# main.net
KiCad netlist of a schematic drawn in EAGLE
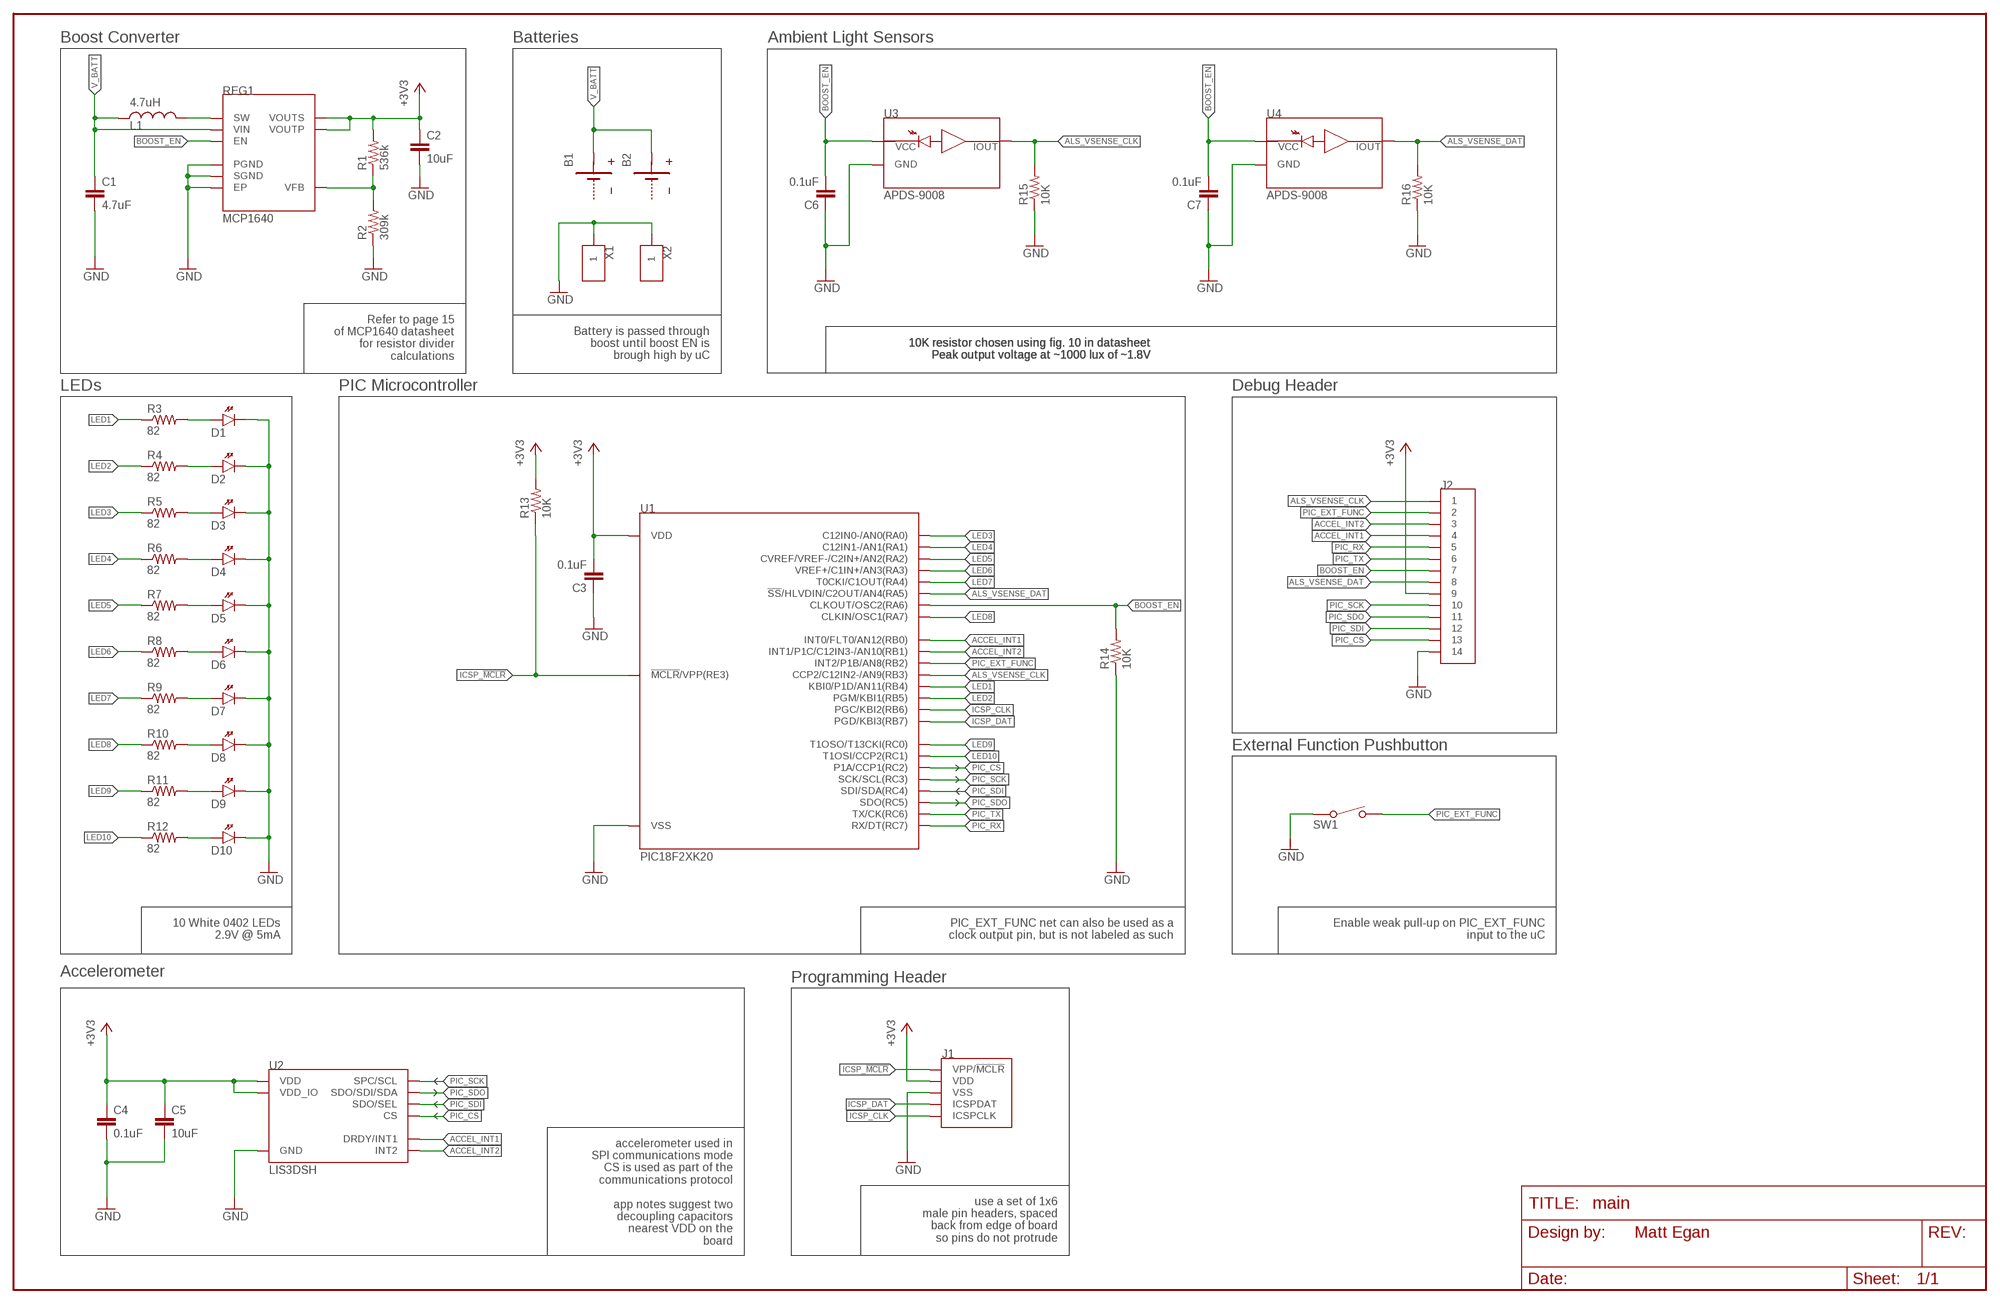
[diagram p0: schematic, sheet 1]

(export (version "E")
  (design (tool "Eeschema 10.0.6"))
  (components
    (comp (ref "B1")
      (value "BATTERY-POS-HALF")
      (footprint "eagle-import:CR20XX-PLATED")
      (libsource (lib "eagle-import") (part "BATTERY-POS-HALF"))
    )
    (comp (ref "B2")
      (value "BATTERY-POS-HALF")
      (footprint "eagle-import:CR20XX-PLATED")
      (libsource (lib "eagle-import") (part "BATTERY-POS-HALF"))
    )
    (comp (ref "C1")
      (value "4.7uF")
      (footprint "eagle-import:SMD-0603")
      (libsource (lib "eagle-import") (part "CAPACITOR0603"))
    )
    (comp (ref "C2")
      (value "10uF")
      (footprint "eagle-import:SMD-0603")
      (libsource (lib "eagle-import") (part "CAPACITOR0603"))
    )
    (comp (ref "C3")
      (value "0.1uF")
      (footprint "eagle-import:SMD-0805")
      (libsource (lib "eagle-import") (part "CAPACITOR0805"))
    )
    (comp (ref "C4")
      (value "0.1uF")
      (footprint "eagle-import:SMD-0805")
      (libsource (lib "eagle-import") (part "CAPACITOR0805"))
    )
    (comp (ref "C5")
      (value "10uF")
      (footprint "eagle-import:SMD-0805")
      (libsource (lib "eagle-import") (part "CAPACITOR0805"))
    )
    (comp (ref "C6")
      (value "0.1uF")
      (footprint "eagle-import:SMD-0805")
      (libsource (lib "eagle-import") (part "CAPACITOR0805"))
    )
    (comp (ref "C7")
      (value "0.1uF")
      (footprint "eagle-import:SMD-0805")
      (libsource (lib "eagle-import") (part "CAPACITOR0805"))
    )
    (comp (ref "D1")
      (value "LED0603")
      (footprint "eagle-import:SMD-0603-P")
      (libsource (lib "eagle-import") (part "LED0603"))
    )
    (comp (ref "D2")
      (value "LED0603")
      (footprint "eagle-import:SMD-0603-P")
      (libsource (lib "eagle-import") (part "LED0603"))
    )
    (comp (ref "D3")
      (value "LED0603")
      (footprint "eagle-import:SMD-0603-P")
      (libsource (lib "eagle-import") (part "LED0603"))
    )
    (comp (ref "D4")
      (value "LED0603")
      (footprint "eagle-import:SMD-0603-P")
      (libsource (lib "eagle-import") (part "LED0603"))
    )
    (comp (ref "D5")
      (value "LED0603")
      (footprint "eagle-import:SMD-0603-P")
      (libsource (lib "eagle-import") (part "LED0603"))
    )
    (comp (ref "D6")
      (value "LED0603")
      (footprint "eagle-import:SMD-0603-P")
      (libsource (lib "eagle-import") (part "LED0603"))
    )
    (comp (ref "D7")
      (value "LED0603")
      (footprint "eagle-import:SMD-0603-P")
      (libsource (lib "eagle-import") (part "LED0603"))
    )
    (comp (ref "D8")
      (value "LED0603")
      (footprint "eagle-import:SMD-0603-P")
      (libsource (lib "eagle-import") (part "LED0603"))
    )
    (comp (ref "D9")
      (value "LED0603")
      (footprint "eagle-import:SMD-0603-P")
      (libsource (lib "eagle-import") (part "LED0603"))
    )
    (comp (ref "D10")
      (value "LED0603")
      (footprint "eagle-import:SMD-0603-P")
      (libsource (lib "eagle-import") (part "LED0603"))
    )
    (comp (ref "J1")
      (value "ICSP-HEADER1X6-0.1-ICSP-PADS")
      (footprint "eagle-import:1X6-0.1-ICSP-PADS")
      (libsource (lib "eagle-import") (part "ICSP-HEADER1X6-0.1-ICSP-PADS"))
    )
    (comp (ref "J2")
      (value "HEADER-141X14-0.05-PADS")
      (footprint "eagle-import:1X14-0.05-PADS")
      (libsource (lib "eagle-import") (part "HEADER-141X14-0.05-PADS"))
    )
    (comp (ref "L1")
      (value "4.7uH")
      (footprint "eagle-import:VLF403210MT")
      (libsource (lib "eagle-import") (part "INDUCTOR"))
    )
    (comp (ref "R1")
      (value "536k")
      (footprint "eagle-import:SMD-0603")
      (libsource (lib "eagle-import") (part "RESISTOR0603"))
    )
    (comp (ref "R2")
      (value "309k")
      (footprint "eagle-import:SMD-0603")
      (libsource (lib "eagle-import") (part "RESISTOR0603"))
    )
    (comp (ref "R3")
      (value "82")
      (footprint "eagle-import:SMD-0603")
      (libsource (lib "eagle-import") (part "RESISTOR0603"))
    )
    (comp (ref "R4")
      (value "82")
      (footprint "eagle-import:SMD-0603")
      (libsource (lib "eagle-import") (part "RESISTOR0603"))
    )
    (comp (ref "R5")
      (value "82")
      (footprint "eagle-import:SMD-0603")
      (libsource (lib "eagle-import") (part "RESISTOR0603"))
    )
    (comp (ref "R6")
      (value "82")
      (footprint "eagle-import:SMD-0603")
      (libsource (lib "eagle-import") (part "RESISTOR0603"))
    )
    (comp (ref "R7")
      (value "82")
      (footprint "eagle-import:SMD-0603")
      (libsource (lib "eagle-import") (part "RESISTOR0603"))
    )
    (comp (ref "R8")
      (value "82")
      (footprint "eagle-import:SMD-0603")
      (libsource (lib "eagle-import") (part "RESISTOR0603"))
    )
    (comp (ref "R9")
      (value "82")
      (footprint "eagle-import:SMD-0603")
      (libsource (lib "eagle-import") (part "RESISTOR0603"))
    )
    (comp (ref "R10")
      (value "82")
      (footprint "eagle-import:SMD-0603")
      (libsource (lib "eagle-import") (part "RESISTOR0603"))
    )
    (comp (ref "R11")
      (value "82")
      (footprint "eagle-import:SMD-0603")
      (libsource (lib "eagle-import") (part "RESISTOR0603"))
    )
    (comp (ref "R12")
      (value "82")
      (footprint "eagle-import:SMD-0603")
      (libsource (lib "eagle-import") (part "RESISTOR0603"))
    )
    (comp (ref "R13")
      (value "10K")
      (footprint "eagle-import:SMD-0603")
      (libsource (lib "eagle-import") (part "RESISTOR0603"))
    )
    (comp (ref "R14")
      (value "10K")
      (footprint "eagle-import:SMD-0603")
      (libsource (lib "eagle-import") (part "RESISTOR0603"))
    )
    (comp (ref "R15")
      (value "10K")
      (footprint "eagle-import:SMD-0603")
      (libsource (lib "eagle-import") (part "RESISTOR0603"))
    )
    (comp (ref "R16")
      (value "10K")
      (footprint "eagle-import:SMD-0603")
      (libsource (lib "eagle-import") (part "RESISTOR0603"))
    )
    (comp (ref "REG1")
      (value "MCP1640")
      (footprint "eagle-import:DFN-8(2X3)")
      (libsource (lib "eagle-import") (part "MCP1640"))
    )
    (comp (ref "SW1")
      (value "B3U-3000P")
      (footprint "eagle-import:B3U-3000P")
      (libsource (lib "eagle-import") (part "B3U-3000P"))
    )
    (comp (ref "U1")
      (value "PIC18F2XK20")
      (footprint "eagle-import:QFN-28")
      (libsource (lib "eagle-import") (part "PIC18F2XK20"))
    )
    (comp (ref "U2")
      (value "LIS3DSH")
      (footprint "eagle-import:LGA-16")
      (libsource (lib "eagle-import") (part "LIS3DSH"))
    )
    (comp (ref "U3")
      (value "APDS-9008")
      (footprint "eagle-import:AVAGO-CHIPLED6")
      (libsource (lib "eagle-import") (part "APDS-9008"))
    )
    (comp (ref "U4")
      (value "APDS-9008")
      (footprint "eagle-import:AVAGO-CHIPLED6")
      (libsource (lib "eagle-import") (part "APDS-9008"))
    )
    (comp (ref "X1")
      (value "TE-2199248-X")
      (footprint "eagle-import:TE-2199248-X")
      (libsource (lib "eagle-import") (part "TE-2199248-X"))
    )
    (comp (ref "X2")
      (value "TE-2199248-X")
      (footprint "eagle-import:TE-2199248-X")
      (libsource (lib "eagle-import") (part "TE-2199248-X"))
    )
  )
  (nets
    (net (code "1") (name "+3V3") (class "Default")
      (node (ref "C2") (pin "1") (pinfunction "1_1") (pintype "passive"))
      (node (ref "C3") (pin "2") (pinfunction "2_2") (pintype "passive"))
      (node (ref "C4") (pin "1") (pinfunction "1_1") (pintype "passive"))
      (node (ref "C5") (pin "1") (pinfunction "1_1") (pintype "passive"))
      (node (ref "J1") (pin "P$2") (pinfunction "VDD_P$2") (pintype "bidirectional"))
      (node (ref "J2") (pin "P$9") (pinfunction "9_P$9") (pintype "bidirectional"))
      (node (ref "R1") (pin "2") (pinfunction "2_2") (pintype "passive"))
      (node (ref "R13") (pin "2") (pinfunction "2_2") (pintype "passive"))
      (node (ref "REG1") (pin "6") (pinfunction "VOUTP_6") (pintype "bidirectional"))
      (node (ref "REG1") (pin "7") (pinfunction "VOUTS_7") (pintype "bidirectional"))
      (node (ref "U1") (pin "P$17") (pinfunction "VDD_P$17") (pintype "bidirectional"))
      (node (ref "U2") (pin "P$1") (pinfunction "VDD_IO_P$1") (pintype "power_in"))
      (node (ref "U2") (pin "P$14") (pinfunction "VDD_P$14") (pintype "power_in"))
      (node (ref "U2") (pin "P$15") (pinfunction "VDD_P$15") (pintype "power_in"))
    )
    (net (code "2") (name "/ICSP_~{MCLR}") (class "Default")
      (node (ref "J1") (pin "P$1") (pinfunction "VPP/~{MCLR}_P$1") (pintype "bidirectional"))
      (node (ref "R13") (pin "1") (pinfunction "1_1") (pintype "passive"))
      (node (ref "U1") (pin "P$26") (pinfunction "~{MCLR}/VPP(RE3)_P$26") (pintype "bidirectional"))
    )
    (net (code "3") (name "ACCEL_INT1") (class "Default")
      (node (ref "J2") (pin "P$4") (pinfunction "4_P$4") (pintype "bidirectional"))
      (node (ref "U1") (pin "P$18") (pinfunction "INT0/FLT0/AN12(RB0)_P$18") (pintype "bidirectional"))
      (node (ref "U2") (pin "P$11") (pinfunction "DRDY/INT1_P$11") (pintype "bidirectional"))
    )
    (net (code "4") (name "ACCEL_INT2") (class "Default")
      (node (ref "J2") (pin "P$3") (pinfunction "3_P$3") (pintype "bidirectional"))
      (node (ref "U1") (pin "P$19") (pinfunction "INT1/P1C/C12IN3-/AN10(RB1)_P$19") (pintype "bidirectional"))
      (node (ref "U2") (pin "P$9") (pinfunction "INT2_P$9") (pintype "bidirectional"))
    )
    (net (code "5") (name "ALS_VSENSE_CLK") (class "Default")
      (node (ref "J2") (pin "P$1") (pinfunction "1_P$1") (pintype "bidirectional"))
      (node (ref "R15") (pin "2") (pinfunction "2_2") (pintype "passive"))
      (node (ref "U1") (pin "P$21") (pinfunction "CCP2/C12IN2-/AN9(RB3)_P$21") (pintype "bidirectional"))
      (node (ref "U3") (pin "P$6") (pinfunction "P$IOUT_P$6") (pintype "bidirectional"))
    )
    (net (code "6") (name "ALS_VSENSE_DAT") (class "Default")
      (node (ref "J2") (pin "P$8") (pinfunction "8_P$8") (pintype "bidirectional"))
      (node (ref "R16") (pin "2") (pinfunction "2_2") (pintype "passive"))
      (node (ref "U1") (pin "P$4") (pinfunction "~{SS}/HLVDIN/C2OUT/AN4(RA5)_P$4") (pintype "bidirectional"))
      (node (ref "U4") (pin "P$6") (pinfunction "P$IOUT_P$6") (pintype "bidirectional"))
    )
    (net (code "7") (name "BOOST_EN") (class "Default")
      (node (ref "C6") (pin "2") (pinfunction "2_2") (pintype "passive"))
      (node (ref "C7") (pin "2") (pinfunction "2_2") (pintype "passive"))
      (node (ref "J2") (pin "P$7") (pinfunction "7_P$7") (pintype "bidirectional"))
      (node (ref "R14") (pin "2") (pinfunction "2_2") (pintype "passive"))
      (node (ref "REG1") (pin "4") (pinfunction "EN_4") (pintype "bidirectional"))
      (node (ref "U1") (pin "P$7") (pinfunction "CLKOUT/OSC2(RA6)_P$7") (pintype "bidirectional"))
      (node (ref "U3") (pin "P$1") (pinfunction "P$VCC_P$1") (pintype "bidirectional"))
      (node (ref "U4") (pin "P$1") (pinfunction "P$VCC_P$1") (pintype "bidirectional"))
    )
    (net (code "8") (name "GND") (class "Default")
      (node (ref "C1") (pin "2") (pinfunction "2_2") (pintype "passive"))
      (node (ref "C2") (pin "2") (pinfunction "2_2") (pintype "passive"))
      (node (ref "C3") (pin "1") (pinfunction "1_1") (pintype "passive"))
      (node (ref "C4") (pin "2") (pinfunction "2_2") (pintype "passive"))
      (node (ref "C5") (pin "2") (pinfunction "2_2") (pintype "passive"))
      (node (ref "C6") (pin "1") (pinfunction "1_1") (pintype "passive"))
      (node (ref "C7") (pin "1") (pinfunction "1_1") (pintype "passive"))
      (node (ref "D1") (pin "-") (pinfunction "-_-") (pintype "bidirectional"))
      (node (ref "D10") (pin "-") (pinfunction "-_-") (pintype "bidirectional"))
      (node (ref "D2") (pin "-") (pinfunction "-_-") (pintype "bidirectional"))
      (node (ref "D3") (pin "-") (pinfunction "-_-") (pintype "bidirectional"))
      (node (ref "D4") (pin "-") (pinfunction "-_-") (pintype "bidirectional"))
      (node (ref "D5") (pin "-") (pinfunction "-_-") (pintype "bidirectional"))
      (node (ref "D6") (pin "-") (pinfunction "-_-") (pintype "bidirectional"))
      (node (ref "D7") (pin "-") (pinfunction "-_-") (pintype "bidirectional"))
      (node (ref "D8") (pin "-") (pinfunction "-_-") (pintype "bidirectional"))
      (node (ref "D9") (pin "-") (pinfunction "-_-") (pintype "bidirectional"))
      (node (ref "J1") (pin "P$3") (pinfunction "VSS_P$3") (pintype "bidirectional"))
      (node (ref "J2") (pin "P$14") (pinfunction "14_P$14") (pintype "bidirectional"))
      (node (ref "R14") (pin "1") (pinfunction "1_1") (pintype "passive"))
      (node (ref "R15") (pin "1") (pinfunction "1_1") (pintype "passive"))
      (node (ref "R16") (pin "1") (pinfunction "1_1") (pintype "passive"))
      (node (ref "R2") (pin "1") (pinfunction "1_1") (pintype "passive"))
      (node (ref "REG1") (pin "2") (pinfunction "SGND_2") (pintype "bidirectional"))
      (node (ref "REG1") (pin "3") (pinfunction "PGND_3") (pintype "bidirectional"))
      (node (ref "REG1") (pin "EP") (pinfunction "EP_EP") (pintype "bidirectional"))
      (node (ref "SW1") (pin "SW$1") (pinfunction "1_SW$1") (pintype "bidirectional"))
      (node (ref "U1") (pin "P$16") (pinfunction "VSS_P$16") (pintype "bidirectional"))
      (node (ref "U1") (pin "P$5") (pinfunction "VSS_P$5") (pintype "bidirectional"))
      (node (ref "U2") (pin "P$10") (pinfunction "GND_P$10") (pintype "power_in"))
      (node (ref "U2") (pin "P$12") (pinfunction "GND_P$12") (pintype "power_in"))
      (node (ref "U2") (pin "P$13") (pinfunction "GND_P$13") (pintype "power_in"))
      (node (ref "U2") (pin "P$16") (pinfunction "GND_P$16") (pintype "power_in"))
      (node (ref "U2") (pin "P$5") (pinfunction "GND_P$5") (pintype "power_in"))
      (node (ref "U3") (pin "P$4") (pinfunction "GND_P$4") (pintype "bidirectional"))
      (node (ref "U4") (pin "P$4") (pinfunction "GND_P$4") (pintype "bidirectional"))
      (node (ref "X1") (pin "P$1") (pinfunction "1_P$1") (pintype "bidirectional"))
      (node (ref "X1") (pin "P$2") (pinfunction "1_P$2") (pintype "bidirectional"))
      (node (ref "X2") (pin "P$1") (pinfunction "1_P$1") (pintype "bidirectional"))
      (node (ref "X2") (pin "P$2") (pinfunction "1_P$2") (pintype "bidirectional"))
    )
    (net (code "9") (name "ICSP_CLK") (class "Default")
      (node (ref "J1") (pin "P$5") (pinfunction "ICSPCLK_P$5") (pintype "bidirectional"))
      (node (ref "U1") (pin "P$24") (pinfunction "PGC/KBI2(RB6)_P$24") (pintype "bidirectional"))
    )
    (net (code "10") (name "ICSP_DAT") (class "Default")
      (node (ref "J1") (pin "P$4") (pinfunction "ICSPDAT_P$4") (pintype "bidirectional"))
      (node (ref "U1") (pin "P$25") (pinfunction "PGD/KBI3(RB7)_P$25") (pintype "bidirectional"))
    )
    (net (code "11") (name "LED1") (class "Default")
      (node (ref "R3") (pin "1") (pinfunction "1_1") (pintype "passive"))
      (node (ref "U1") (pin "P$22") (pinfunction "KBI0/P1D/AN11(RB4)_P$22") (pintype "bidirectional"))
    )
    (net (code "12") (name "LED2") (class "Default")
      (node (ref "R4") (pin "1") (pinfunction "1_1") (pintype "passive"))
      (node (ref "U1") (pin "P$23") (pinfunction "PGM/KBI1(RB5)_P$23") (pintype "bidirectional"))
    )
    (net (code "13") (name "LED3") (class "Default")
      (node (ref "R5") (pin "1") (pinfunction "1_1") (pintype "passive"))
      (node (ref "U1") (pin "P$27") (pinfunction "C12IN0-/AN0(RA0)_P$27") (pintype "bidirectional"))
    )
    (net (code "14") (name "LED4") (class "Default")
      (node (ref "R6") (pin "1") (pinfunction "1_1") (pintype "passive"))
      (node (ref "U1") (pin "P$28") (pinfunction "C12IN1-/AN1(RA1)_P$28") (pintype "bidirectional"))
    )
    (net (code "15") (name "LED5") (class "Default")
      (node (ref "R7") (pin "1") (pinfunction "1_1") (pintype "passive"))
      (node (ref "U1") (pin "P$1") (pinfunction "CVREF/VREF-/C2IN+/AN2(RA2)_P$1") (pintype "bidirectional"))
    )
    (net (code "16") (name "LED6") (class "Default")
      (node (ref "R8") (pin "1") (pinfunction "1_1") (pintype "passive"))
      (node (ref "U1") (pin "P$2") (pinfunction "VREF+/C1IN+/AN3(RA3)_P$2") (pintype "bidirectional"))
    )
    (net (code "17") (name "LED7") (class "Default")
      (node (ref "R9") (pin "1") (pinfunction "1_1") (pintype "passive"))
      (node (ref "U1") (pin "P$3") (pinfunction "T0CKI/C1OUT(RA4)_P$3") (pintype "bidirectional"))
    )
    (net (code "18") (name "LED8") (class "Default")
      (node (ref "R10") (pin "1") (pinfunction "1_1") (pintype "passive"))
      (node (ref "U1") (pin "P$6") (pinfunction "CLKIN/OSC1(RA7)_P$6") (pintype "bidirectional"))
    )
    (net (code "19") (name "LED9") (class "Default")
      (node (ref "R11") (pin "1") (pinfunction "1_1") (pintype "passive"))
      (node (ref "U1") (pin "P$8") (pinfunction "T1OSO/T13CKI(RC0)_P$8") (pintype "bidirectional"))
    )
    (net (code "20") (name "LED10") (class "Default")
      (node (ref "R12") (pin "1") (pinfunction "1_1") (pintype "passive"))
      (node (ref "U1") (pin "P$9") (pinfunction "T1OSI/CCP2(RC1)_P$9") (pintype "bidirectional"))
    )
    (net (code "21") (name "Net-(D1-Pad+)") (class "Default")
      (node (ref "D1") (pin "+") (pinfunction "+_+") (pintype "input"))
      (node (ref "R3") (pin "2") (pinfunction "2_2") (pintype "passive"))
    )
    (net (code "22") (name "Net-(D2-Pad+)") (class "Default")
      (node (ref "D2") (pin "+") (pinfunction "+_+") (pintype "input"))
      (node (ref "R4") (pin "2") (pinfunction "2_2") (pintype "passive"))
    )
    (net (code "23") (name "Net-(D3-Pad+)") (class "Default")
      (node (ref "D3") (pin "+") (pinfunction "+_+") (pintype "input"))
      (node (ref "R5") (pin "2") (pinfunction "2_2") (pintype "passive"))
    )
    (net (code "24") (name "Net-(D4-Pad+)") (class "Default")
      (node (ref "D4") (pin "+") (pinfunction "+_+") (pintype "input"))
      (node (ref "R6") (pin "2") (pinfunction "2_2") (pintype "passive"))
    )
    (net (code "25") (name "Net-(D5-Pad+)") (class "Default")
      (node (ref "D5") (pin "+") (pinfunction "+_+") (pintype "input"))
      (node (ref "R7") (pin "2") (pinfunction "2_2") (pintype "passive"))
    )
    (net (code "26") (name "Net-(D6-Pad+)") (class "Default")
      (node (ref "D6") (pin "+") (pinfunction "+_+") (pintype "input"))
      (node (ref "R8") (pin "2") (pinfunction "2_2") (pintype "passive"))
    )
    (net (code "27") (name "Net-(D7-Pad+)") (class "Default")
      (node (ref "D7") (pin "+") (pinfunction "+_+") (pintype "input"))
      (node (ref "R9") (pin "2") (pinfunction "2_2") (pintype "passive"))
    )
    (net (code "28") (name "Net-(D8-Pad+)") (class "Default")
      (node (ref "D8") (pin "+") (pinfunction "+_+") (pintype "input"))
      (node (ref "R10") (pin "2") (pinfunction "2_2") (pintype "passive"))
    )
    (net (code "29") (name "Net-(D9-Pad+)") (class "Default")
      (node (ref "D9") (pin "+") (pinfunction "+_+") (pintype "input"))
      (node (ref "R11") (pin "2") (pinfunction "2_2") (pintype "passive"))
    )
    (net (code "30") (name "Net-(D10-Pad+)") (class "Default")
      (node (ref "D10") (pin "+") (pinfunction "+_+") (pintype "input"))
      (node (ref "R12") (pin "2") (pinfunction "2_2") (pintype "passive"))
    )
    (net (code "31") (name "Net-(L1-2)") (class "Default")
      (node (ref "L1") (pin "P$2") (pinfunction "2_P$2") (pintype "passive"))
      (node (ref "REG1") (pin "5") (pinfunction "SW_5") (pintype "bidirectional"))
    )
    (net (code "32") (name "Net-(REG1-VFB)") (class "Default")
      (node (ref "R1") (pin "1") (pinfunction "1_1") (pintype "passive"))
      (node (ref "R2") (pin "2") (pinfunction "2_2") (pintype "passive"))
      (node (ref "REG1") (pin "1") (pinfunction "VFB_1") (pintype "bidirectional"))
    )
    (net (code "33") (name "PIC_CS") (class "Default")
      (node (ref "J2") (pin "P$13") (pinfunction "13_P$13") (pintype "bidirectional"))
      (node (ref "U1") (pin "P$10") (pinfunction "P1A/CCP1(RC2)_P$10") (pintype "bidirectional"))
      (node (ref "U2") (pin "P$8") (pinfunction "CS_P$8") (pintype "bidirectional"))
    )
    (net (code "34") (name "PIC_EXT_FUNC") (class "Default")
      (node (ref "J2") (pin "P$2") (pinfunction "2_P$2") (pintype "bidirectional"))
      (node (ref "SW1") (pin "SW$2") (pinfunction "3_SW$2") (pintype "bidirectional"))
      (node (ref "U1") (pin "P$20") (pinfunction "INT2/P1B/AN8(RB2)_P$20") (pintype "bidirectional"))
    )
    (net (code "35") (name "PIC_RX") (class "Default")
      (node (ref "J2") (pin "P$5") (pinfunction "5_P$5") (pintype "bidirectional"))
      (node (ref "U1") (pin "P$15") (pinfunction "RX/DT(RC7)_P$15") (pintype "bidirectional"))
    )
    (net (code "36") (name "PIC_SCK") (class "Default")
      (node (ref "J2") (pin "P$10") (pinfunction "10_P$10") (pintype "bidirectional"))
      (node (ref "U1") (pin "P$11") (pinfunction "SCK/SCL(RC3)_P$11") (pintype "bidirectional"))
      (node (ref "U2") (pin "P$4") (pinfunction "SPC/SCL_P$4") (pintype "bidirectional"))
    )
    (net (code "37") (name "PIC_SDI") (class "Default")
      (node (ref "J2") (pin "P$12") (pinfunction "12_P$12") (pintype "bidirectional"))
      (node (ref "U1") (pin "P$12") (pinfunction "SDI/SDA(RC4)_P$12") (pintype "bidirectional"))
      (node (ref "U2") (pin "P$7") (pinfunction "SDO/SEL_P$7") (pintype "bidirectional"))
    )
    (net (code "38") (name "PIC_SDO") (class "Default")
      (node (ref "J2") (pin "P$11") (pinfunction "11_P$11") (pintype "bidirectional"))
      (node (ref "U1") (pin "P$13") (pinfunction "SDO(RC5)_P$13") (pintype "bidirectional"))
      (node (ref "U2") (pin "P$6") (pinfunction "SDO/SDI/SDA_P$6") (pintype "bidirectional"))
    )
    (net (code "39") (name "PIC_TX") (class "Default")
      (node (ref "J2") (pin "P$6") (pinfunction "6_P$6") (pintype "bidirectional"))
      (node (ref "U1") (pin "P$14") (pinfunction "TX/CK(RC6)_P$14") (pintype "bidirectional"))
    )
    (net (code "40") (name "V_BATT") (class "Default")
      (node (ref "B1") (pin "P$1") (pinfunction "P$+_P$1") (pintype "bidirectional"))
      (node (ref "B2") (pin "P$1") (pinfunction "P$+_P$1") (pintype "bidirectional"))
      (node (ref "C1") (pin "1") (pinfunction "1_1") (pintype "passive"))
      (node (ref "L1") (pin "P$1") (pinfunction "1_P$1") (pintype "passive"))
      (node (ref "REG1") (pin "8") (pinfunction "VIN_8") (pintype "bidirectional"))
    )
  )
)
